# DorothiController.net
KiCad netlist of a schematic drawn in EAGLE
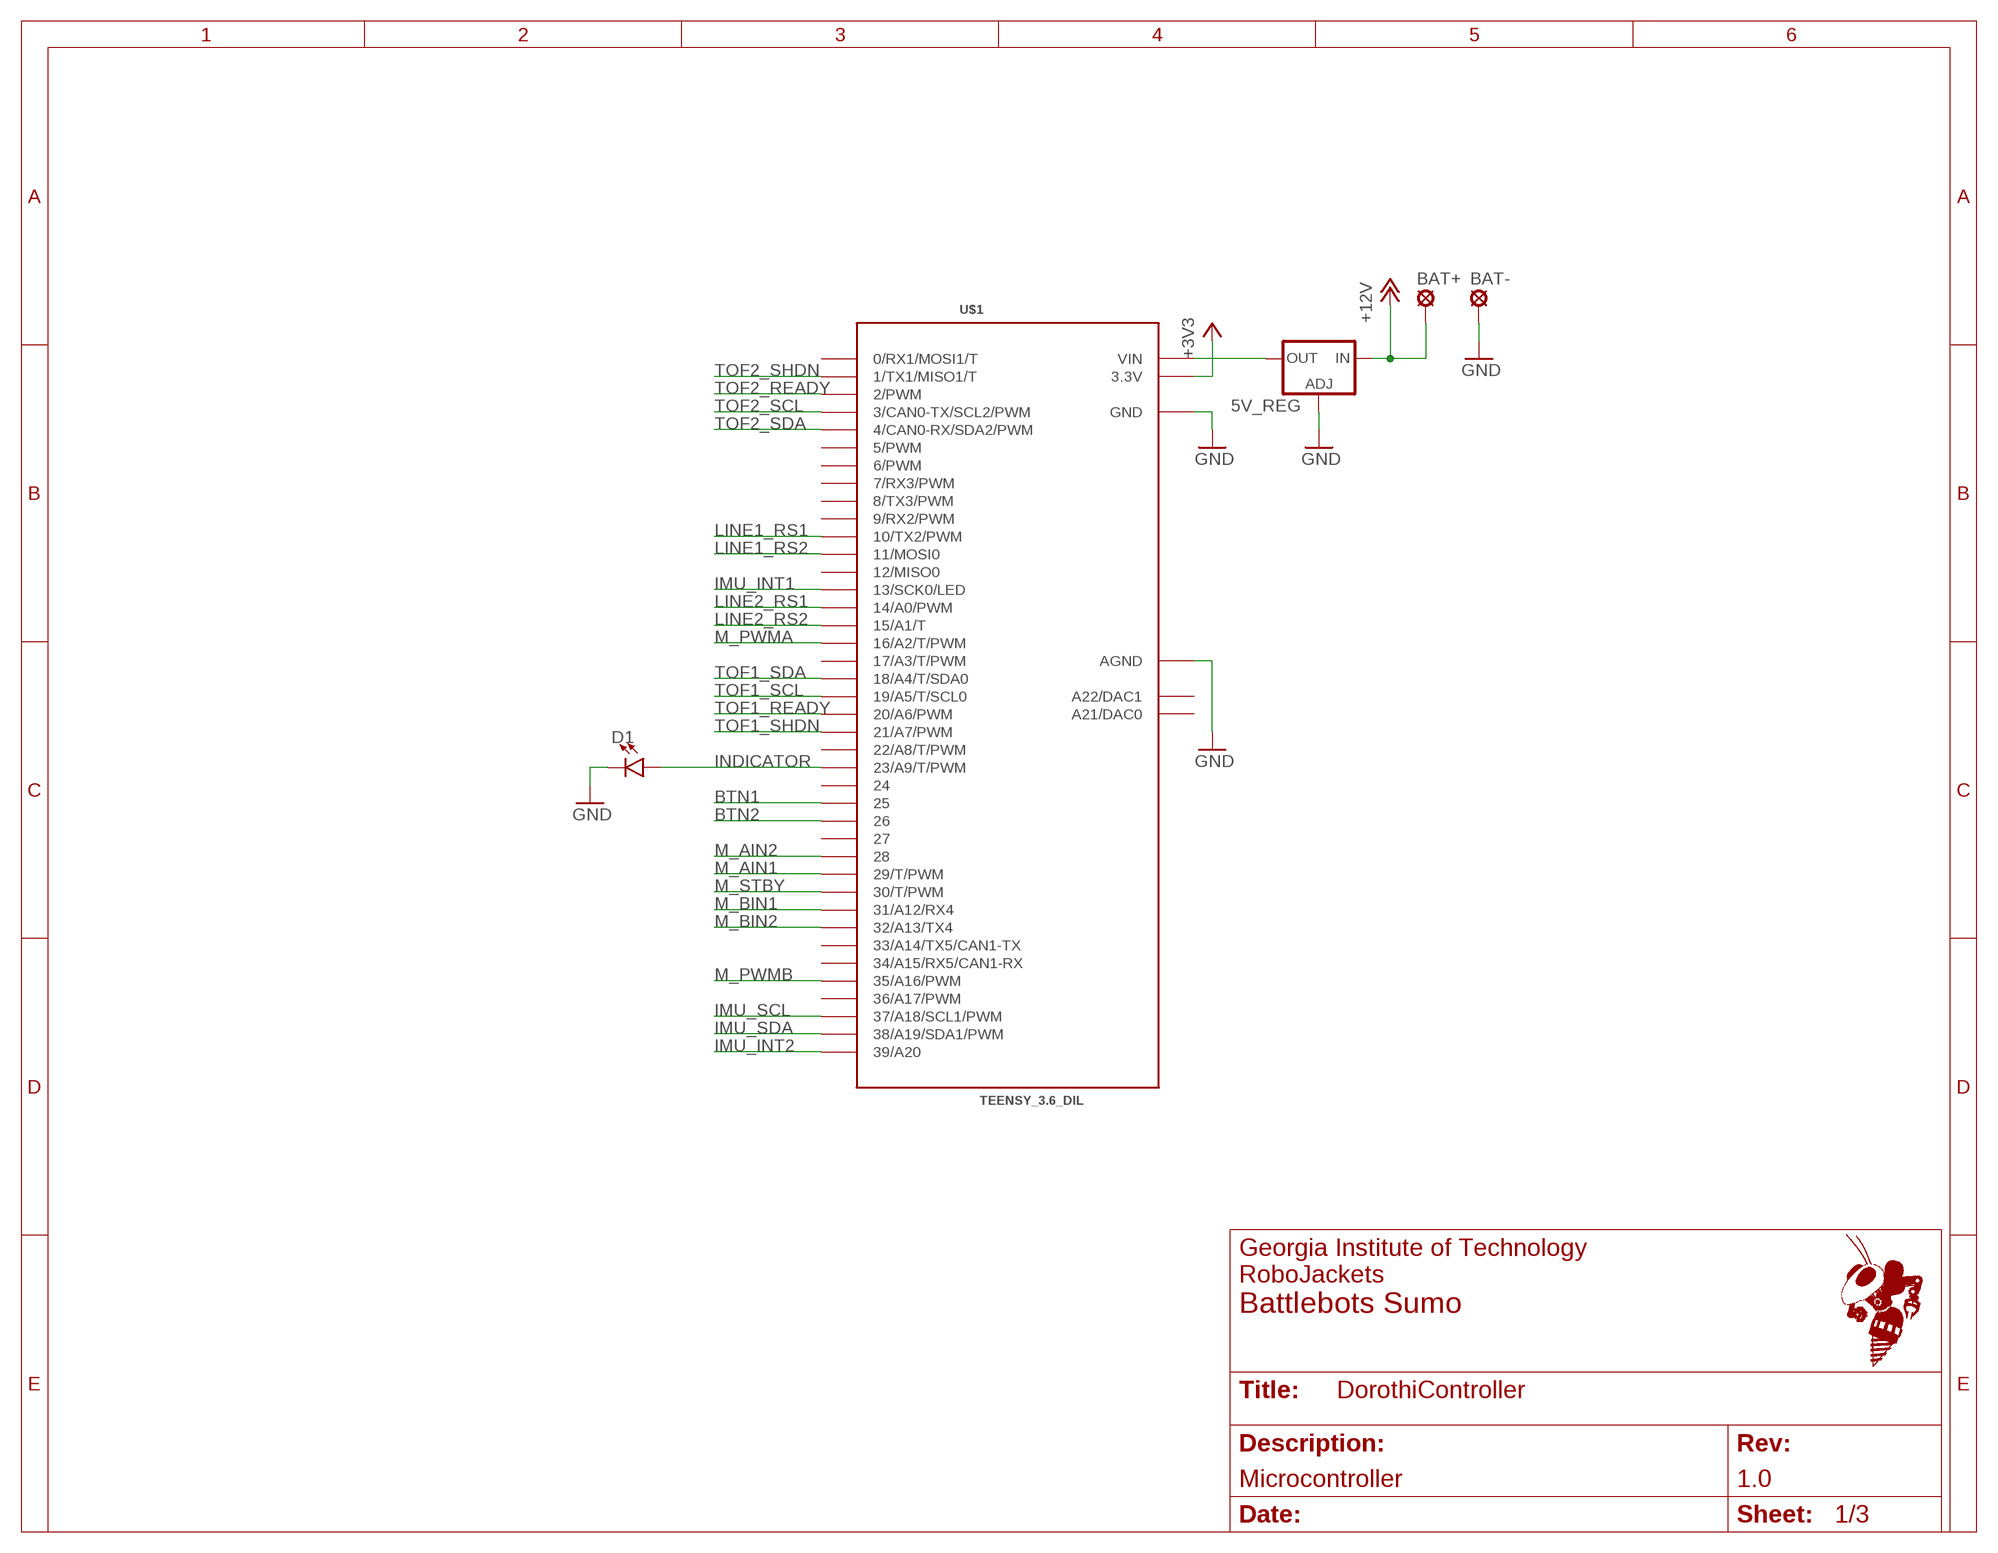
[diagram p0: schematic, sheet 1]
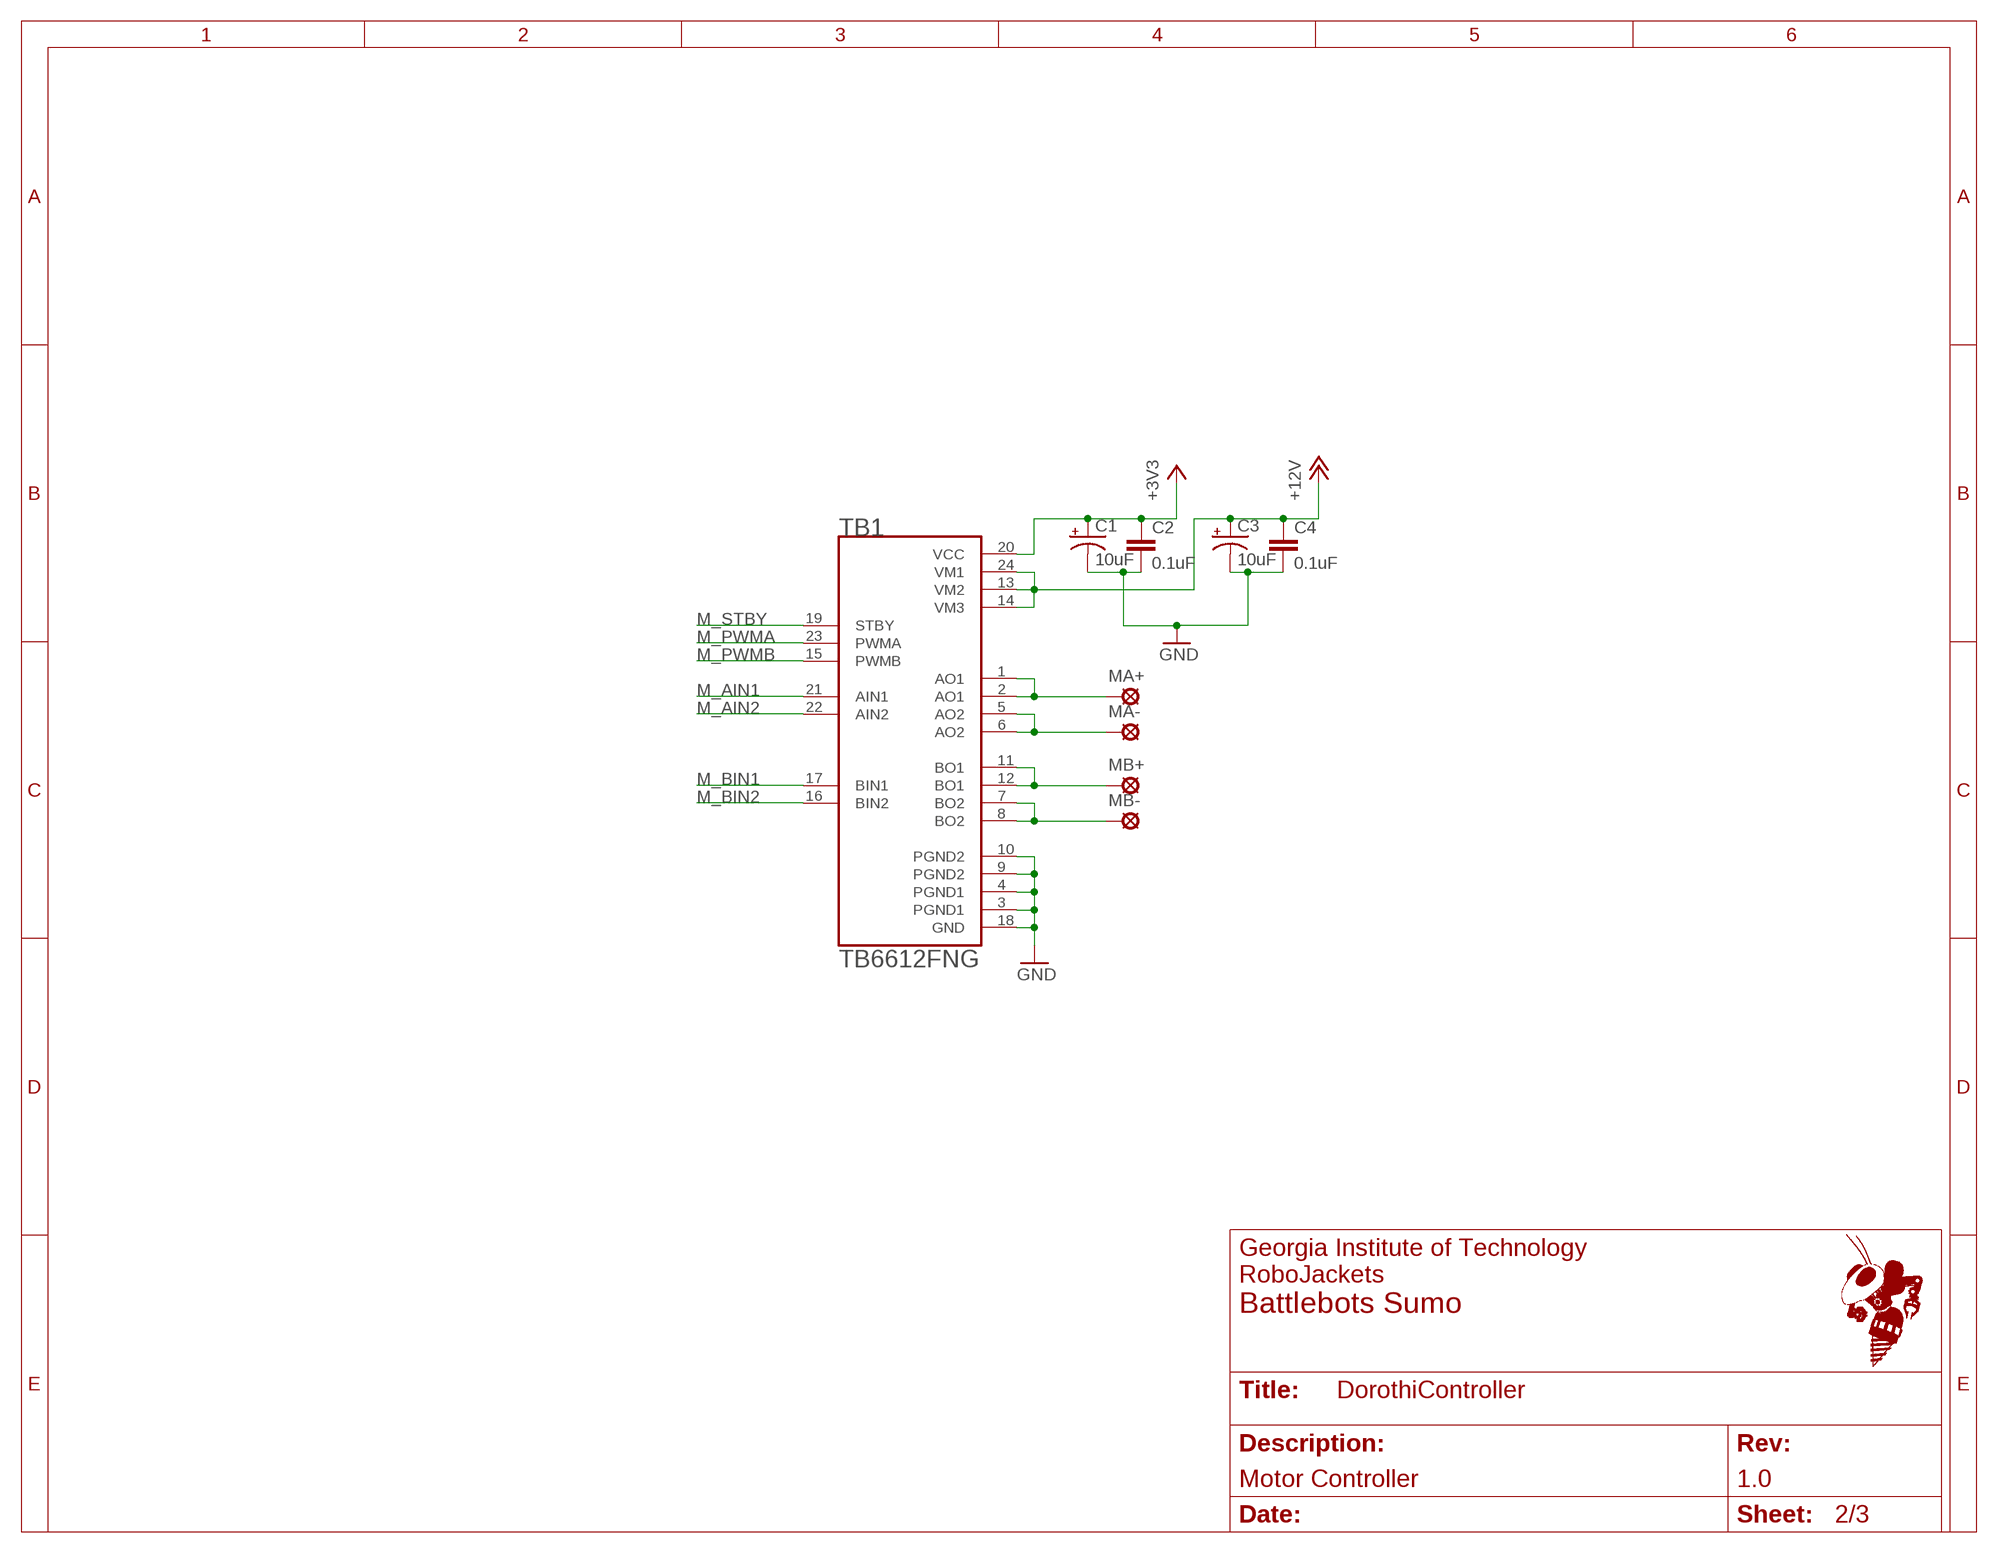
[diagram p1: schematic, sheet 2]
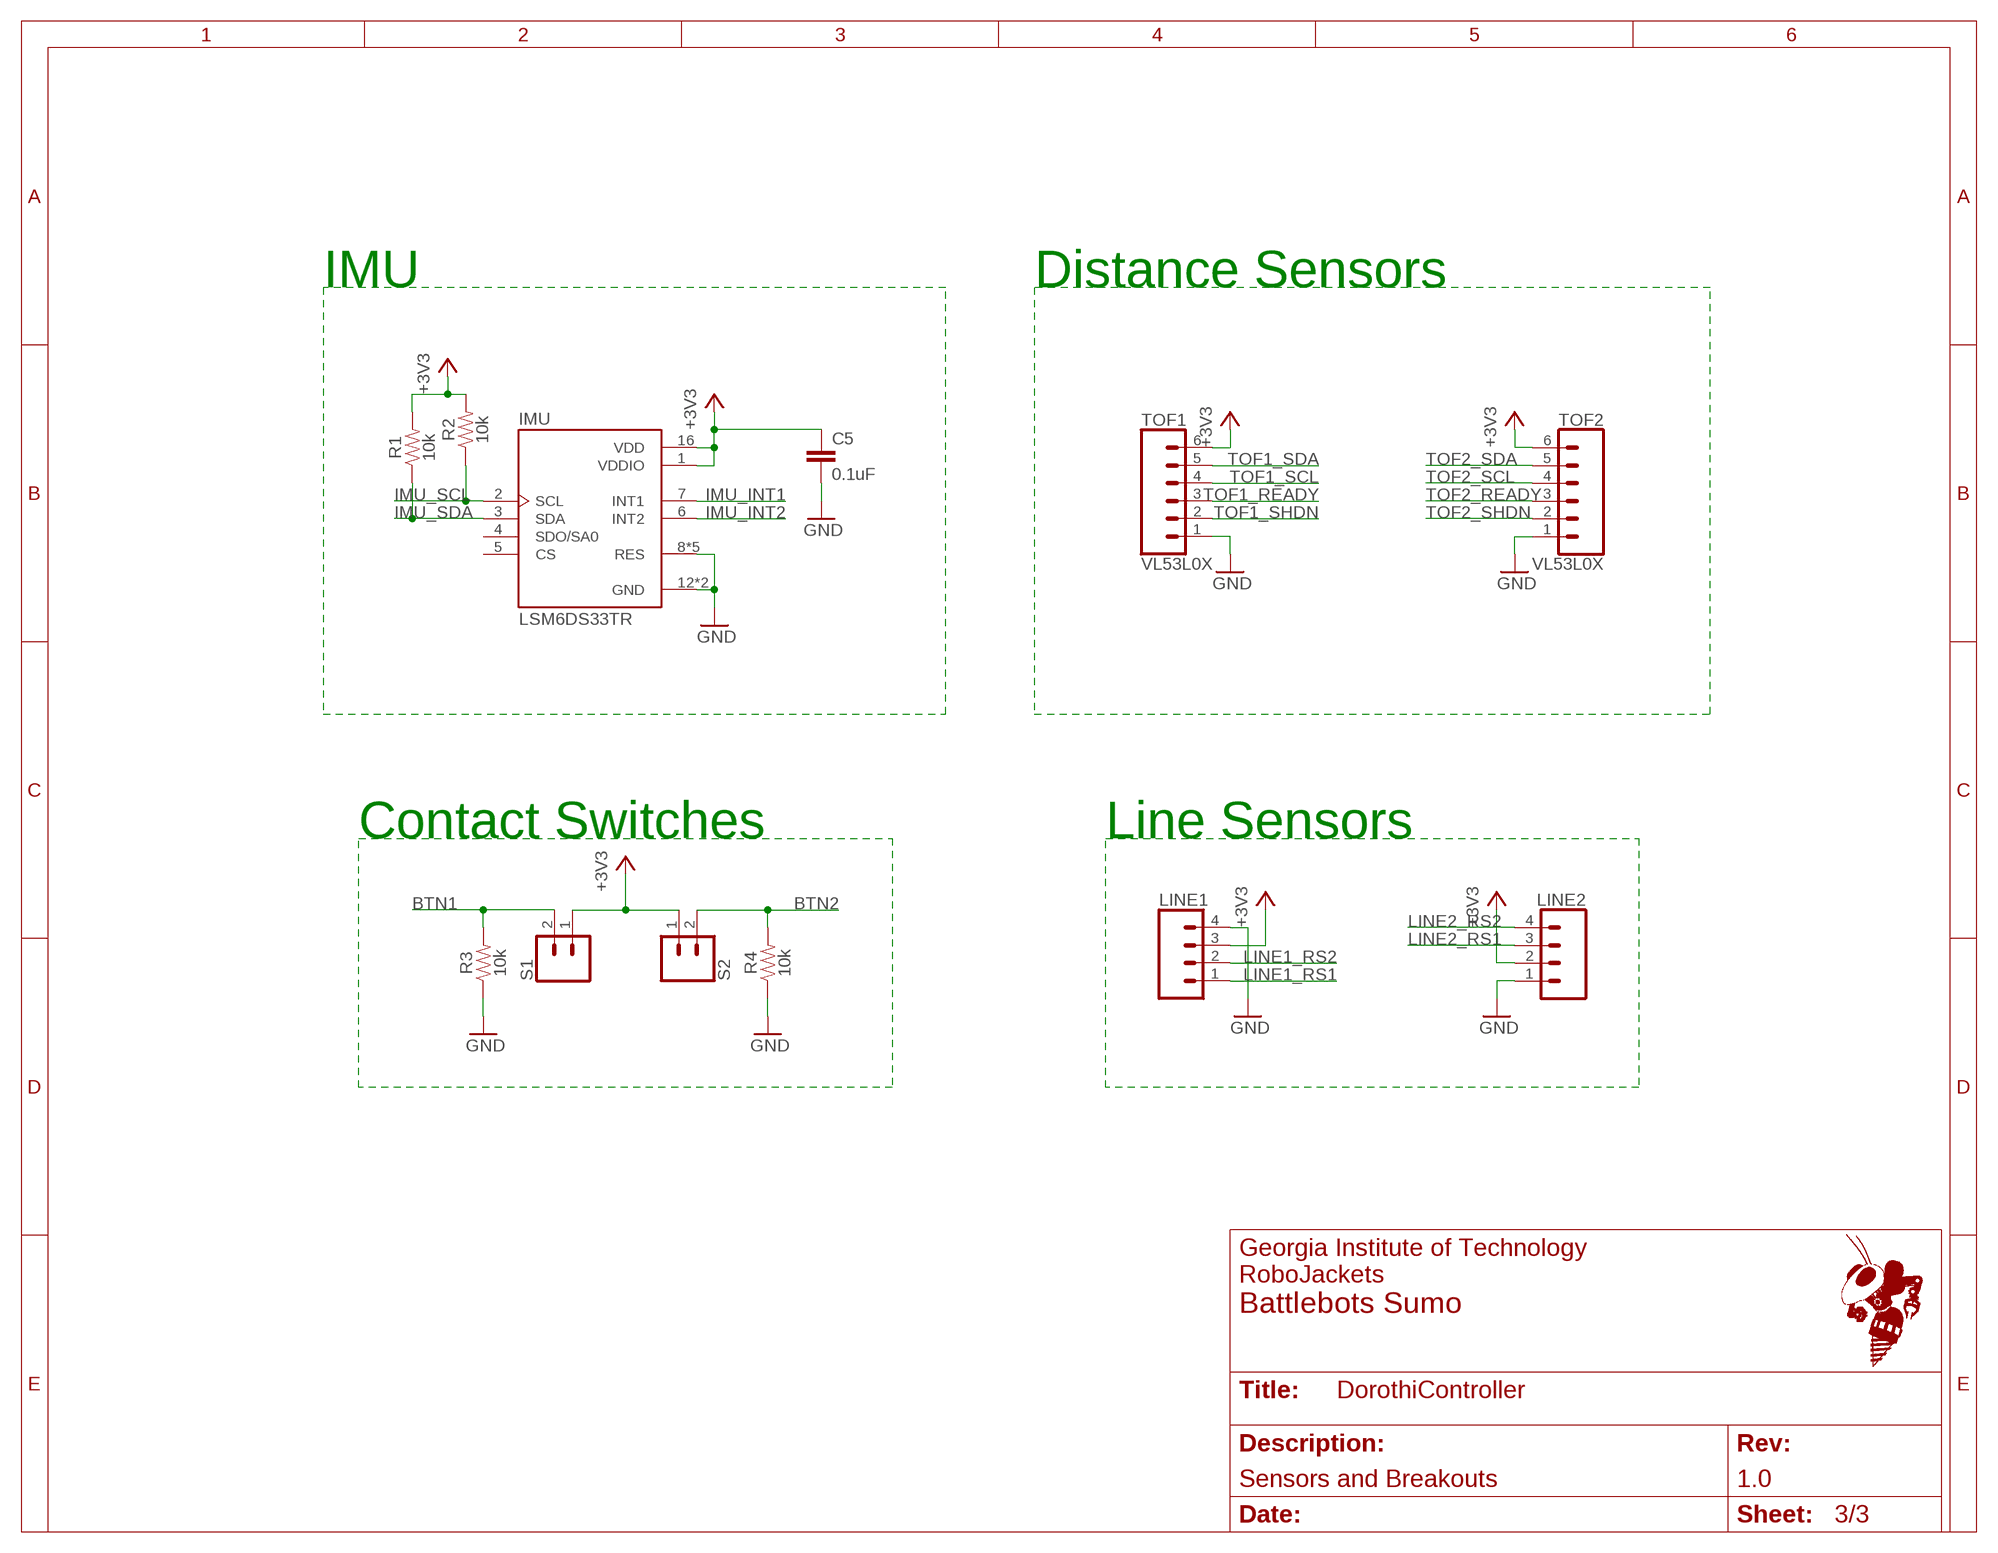
[diagram p2: schematic, sheet 3]

(export (version "E")
  (design (tool "Eeschema 10.0.6"))
  (components
    (comp (ref "5V_REG")
      (value "LM138-TL")
      (footprint "eagle-import:TO220L1")
      (libsource (lib "eagle-import") (part "LM138-TL"))
    )
    (comp (ref "BAT+")
      (value "24_SOLPAD")
      (footprint "eagle-import:WIRE_SOLPAD")
      (libsource (lib "eagle-import") (part "24_SOLPAD"))
    )
    (comp (ref "BAT-")
      (value "24_SOLPAD")
      (footprint "eagle-import:WIRE_SOLPAD")
      (libsource (lib "eagle-import") (part "24_SOLPAD"))
    )
    (comp (ref "D1")
      (value "LED0603")
      (footprint "eagle-import:LED-0603")
      (libsource (lib "eagle-import") (part "LED0603"))
    )
    (comp (ref "U$1")
      (value "TEENSY_3.6_DIL")
      (footprint "eagle-import:TEENSY_3.6_DIL")
      (libsource (lib "eagle-import") (part "TEENSY_3.6_DIL"))
    )
    (comp (ref "C5")
      (value "0.1uF")
      (footprint "eagle-import:0603")
      (libsource (lib "eagle-import") (part "0.1UF-0603-25V-5%"))
    )
    (comp (ref "IMU")
      (value "LSM6DS33TR")
      (footprint "eagle-import:PQFN50P300X300X86-16N")
      (fields (field (name "MF") "STMicroelectronics"))
      (libsource (lib "eagle-import") (part "LSM6DS33TR"))
    )
    (comp (ref "LINE1")
      (value "CONN_04")
      (footprint "eagle-import:1X04")
      (libsource (lib "eagle-import") (part "CONN_04"))
    )
    (comp (ref "LINE2")
      (value "CONN_04")
      (footprint "eagle-import:1X04")
      (libsource (lib "eagle-import") (part "CONN_04"))
    )
    (comp (ref "R1")
      (value "10k")
      (footprint "eagle-import:0603")
      (libsource (lib "eagle-import") (part "10KOHM-0603-1/10W-1%"))
    )
    (comp (ref "R2")
      (value "10k")
      (footprint "eagle-import:0603")
      (libsource (lib "eagle-import") (part "10KOHM-0603-1/10W-1%"))
    )
    (comp (ref "R3")
      (value "10k")
      (footprint "eagle-import:0603")
      (libsource (lib "eagle-import") (part "10KOHM-0603-1/10W-1%"))
    )
    (comp (ref "R4")
      (value "10k")
      (footprint "eagle-import:0603")
      (libsource (lib "eagle-import") (part "10KOHM-0603-1/10W-1%"))
    )
    (comp (ref "S1")
      (value "CONN_02")
      (footprint "eagle-import:1X02")
      (libsource (lib "eagle-import") (part "CONN_02"))
    )
    (comp (ref "S2")
      (value "CONN_02")
      (footprint "eagle-import:1X02")
      (libsource (lib "eagle-import") (part "CONN_02"))
    )
    (comp (ref "TOF1")
      (value "VL53L0X")
      (footprint "eagle-import:1X06")
      (libsource (lib "eagle-import") (part "CONN_06SILK_FEMALE_PTH"))
    )
    (comp (ref "TOF2")
      (value "VL53L0X")
      (footprint "eagle-import:1X06")
      (libsource (lib "eagle-import") (part "CONN_06SILK_FEMALE_PTH"))
    )
    (comp (ref "C1")
      (value "10uF")
      (footprint "eagle-import:EIA3528")
      (libsource (lib "eagle-import") (part "10UF-POLAR-EIA3528-20V-10%(TANT)"))
    )
    (comp (ref "C2")
      (value "0.1uF")
      (footprint "eagle-import:0603")
      (libsource (lib "eagle-import") (part "0.1UF-0603-25V-5%"))
    )
    (comp (ref "C3")
      (value "10uF")
      (footprint "eagle-import:EIA3528")
      (libsource (lib "eagle-import") (part "10UF-POLAR-EIA3528-20V-10%(TANT)"))
    )
    (comp (ref "C4")
      (value "0.1uF")
      (footprint "eagle-import:0603")
      (libsource (lib "eagle-import") (part "0.1UF-0603-25V-5%"))
    )
    (comp (ref "MA+")
      (value "24_SOLPAD")
      (footprint "eagle-import:WIRE_SOLPAD")
      (libsource (lib "eagle-import") (part "24_SOLPAD"))
    )
    (comp (ref "MA-")
      (value "24_SOLPAD")
      (footprint "eagle-import:WIRE_SOLPAD")
      (libsource (lib "eagle-import") (part "24_SOLPAD"))
    )
    (comp (ref "MB+")
      (value "24_SOLPAD")
      (footprint "eagle-import:WIRE_SOLPAD")
      (libsource (lib "eagle-import") (part "24_SOLPAD"))
    )
    (comp (ref "MB-")
      (value "24_SOLPAD")
      (footprint "eagle-import:WIRE_SOLPAD")
      (libsource (lib "eagle-import") (part "24_SOLPAD"))
    )
    (comp (ref "TB1")
      (value "TB6612FNG")
      (footprint "eagle-import:SOP65P760X160-24N")
      (fields (field (name "MF") "Toshiba") (field (name "MP") "TB6612FNG_O,C,8,EL"))
      (libsource (lib "eagle-import") (part "TB6612FNG(O,C,8,EL"))
    )
  )
  (nets
    (net (code "1") (name "+3V3") (class "Default")
      (node (ref "C1") (pin "A") (pinfunction "+_A") (pintype "passive"))
      (node (ref "C2") (pin "1") (pinfunction "1_1") (pintype "passive"))
      (node (ref "C5") (pin "1") (pinfunction "1_1") (pintype "passive"))
      (node (ref "IMU") (pin "1") (pinfunction "VDDIO_1") (pintype "power_in"))
      (node (ref "IMU") (pin "16") (pinfunction "VDD_16") (pintype "power_in"))
      (node (ref "LINE1") (pin "3") (pinfunction "3_3") (pintype "passive"))
      (node (ref "LINE2") (pin "2") (pinfunction "2_2") (pintype "passive"))
      (node (ref "R1") (pin "2") (pinfunction "2_2") (pintype "passive"))
      (node (ref "R2") (pin "2") (pinfunction "2_2") (pintype "passive"))
      (node (ref "S1") (pin "1") (pinfunction "1_1") (pintype "passive"))
      (node (ref "S2") (pin "1") (pinfunction "1_1") (pintype "passive"))
      (node (ref "TB1") (pin "20") (pinfunction "VCC_20") (pintype "power_in"))
      (node (ref "TOF1") (pin "6") (pinfunction "6_6") (pintype "passive"))
      (node (ref "TOF2") (pin "6") (pinfunction "6_6") (pintype "passive"))
      (node (ref "U$1") (pin "3.3V") (pinfunction "3.3V_3.3V") (pintype "power_in"))
      (node (ref "U$1") (pin "3.3V3") (pinfunction "3.3V_3.3V3") (pintype "power_in"))
    )
    (net (code "2") (name "+12V") (class "Default")
      (node (ref "5V_REG") (pin "3") (pinfunction "IN_3") (pintype "input"))
      (node (ref "BAT+") (pin "P$1") (pinfunction "MP_P$1") (pintype "passive"))
      (node (ref "C3") (pin "A") (pinfunction "+_A") (pintype "passive"))
      (node (ref "C4") (pin "1") (pinfunction "1_1") (pintype "passive"))
      (node (ref "TB1") (pin "13") (pinfunction "VM2_13") (pintype "power_in"))
      (node (ref "TB1") (pin "14") (pinfunction "VM3_14") (pintype "power_in"))
      (node (ref "TB1") (pin "24") (pinfunction "VM1_24") (pintype "power_in"))
    )
    (net (code "3") (name "BTN1") (class "Default")
      (node (ref "R3") (pin "2") (pinfunction "2_2") (pintype "passive"))
      (node (ref "S1") (pin "2") (pinfunction "2_2") (pintype "passive"))
      (node (ref "U$1") (pin "25") (pinfunction "25_25") (pintype "bidirectional"))
    )
    (net (code "4") (name "BTN2") (class "Default")
      (node (ref "R4") (pin "2") (pinfunction "2_2") (pintype "passive"))
      (node (ref "S2") (pin "2") (pinfunction "2_2") (pintype "passive"))
      (node (ref "U$1") (pin "26") (pinfunction "26_26") (pintype "bidirectional"))
    )
    (net (code "5") (name "GND") (class "Default")
      (node (ref "5V_REG") (pin "1") (pinfunction "ADJ_1") (pintype "input"))
      (node (ref "BAT-") (pin "P$1") (pinfunction "MP_P$1") (pintype "passive"))
      (node (ref "C1") (pin "C") (pinfunction "-_C") (pintype "passive"))
      (node (ref "C2") (pin "2") (pinfunction "2_2") (pintype "passive"))
      (node (ref "C3") (pin "C") (pinfunction "-_C") (pintype "passive"))
      (node (ref "C4") (pin "2") (pinfunction "2_2") (pintype "passive"))
      (node (ref "C5") (pin "2") (pinfunction "2_2") (pintype "passive"))
      (node (ref "D1") (pin "C") (pinfunction "C_C") (pintype "passive"))
      (node (ref "IMU") (pin "10") (pinfunction "RES_10") (pintype "passive"))
      (node (ref "IMU") (pin "11") (pinfunction "RES_11") (pintype "passive"))
      (node (ref "IMU") (pin "12") (pinfunction "GND_12") (pintype "power_in"))
      (node (ref "IMU") (pin "13") (pinfunction "GND_13") (pintype "power_in"))
      (node (ref "IMU") (pin "15") (pinfunction "RES_15") (pintype "passive"))
      (node (ref "IMU") (pin "8") (pinfunction "RES_8") (pintype "passive"))
      (node (ref "IMU") (pin "9") (pinfunction "RES_9") (pintype "passive"))
      (node (ref "LINE1") (pin "4") (pinfunction "4_4") (pintype "passive"))
      (node (ref "LINE2") (pin "1") (pinfunction "1_1") (pintype "passive"))
      (node (ref "R3") (pin "1") (pinfunction "1_1") (pintype "passive"))
      (node (ref "R4") (pin "1") (pinfunction "1_1") (pintype "passive"))
      (node (ref "TB1") (pin "10") (pinfunction "PGND2_10") (pintype "passive"))
      (node (ref "TB1") (pin "18") (pinfunction "GND_18") (pintype "passive"))
      (node (ref "TB1") (pin "3") (pinfunction "PGND1_3") (pintype "passive"))
      (node (ref "TB1") (pin "4") (pinfunction "PGND1_4") (pintype "passive"))
      (node (ref "TB1") (pin "9") (pinfunction "PGND2_9") (pintype "passive"))
      (node (ref "TOF1") (pin "1") (pinfunction "1_1") (pintype "passive"))
      (node (ref "TOF2") (pin "1") (pinfunction "1_1") (pintype "passive"))
      (node (ref "U$1") (pin "AGND") (pinfunction "AGND_AGND") (pintype "power_in"))
      (node (ref "U$1") (pin "GND") (pinfunction "GND_GND") (pintype "power_in"))
      (node (ref "U$1") (pin "GND1") (pinfunction "GND_GND1") (pintype "power_in"))
    )
    (net (code "6") (name "IMU_INT1") (class "Default")
      (node (ref "IMU") (pin "7") (pinfunction "INT1_7") (pintype "output"))
      (node (ref "U$1") (pin "13") (pinfunction "13/SCK0/LED_13") (pintype "bidirectional"))
    )
    (net (code "7") (name "IMU_INT2") (class "Default")
      (node (ref "IMU") (pin "6") (pinfunction "INT2_6") (pintype "output"))
      (node (ref "U$1") (pin "39/A20") (pinfunction "39/A20_39/A20") (pintype "bidirectional"))
    )
    (net (code "8") (name "IMU_SCL") (class "Default")
      (node (ref "IMU") (pin "2") (pinfunction "SCL_2") (pintype "bidirectional"))
      (node (ref "R2") (pin "1") (pinfunction "1_1") (pintype "passive"))
      (node (ref "U$1") (pin "37/A18") (pinfunction "37/A18/SCL1/PWM_37/A18") (pintype "bidirectional"))
    )
    (net (code "9") (name "IMU_SDA") (class "Default")
      (node (ref "IMU") (pin "3") (pinfunction "SDA_3") (pintype "bidirectional"))
      (node (ref "R1") (pin "1") (pinfunction "1_1") (pintype "passive"))
      (node (ref "U$1") (pin "38/A19") (pinfunction "38/A19/SDA1/PWM_38/A19") (pintype "bidirectional"))
    )
    (net (code "10") (name "INDICATOR") (class "Default")
      (node (ref "D1") (pin "A") (pinfunction "A_A") (pintype "passive"))
      (node (ref "U$1") (pin "23/A9") (pinfunction "23/A9/T/PWM_23/A9") (pintype "bidirectional"))
    )
    (net (code "11") (name "LINE1_RS1") (class "Default")
      (node (ref "LINE1") (pin "1") (pinfunction "1_1") (pintype "passive"))
      (node (ref "U$1") (pin "10") (pinfunction "10/TX2/PWM_10") (pintype "bidirectional"))
    )
    (net (code "12") (name "LINE1_RS2") (class "Default")
      (node (ref "LINE1") (pin "2") (pinfunction "2_2") (pintype "passive"))
      (node (ref "U$1") (pin "11") (pinfunction "11/MOSI0_11") (pintype "bidirectional"))
    )
    (net (code "13") (name "LINE2_RS1") (class "Default")
      (node (ref "LINE2") (pin "3") (pinfunction "3_3") (pintype "passive"))
      (node (ref "U$1") (pin "14/A0") (pinfunction "14/A0/PWM_14/A0") (pintype "bidirectional"))
    )
    (net (code "14") (name "LINE2_RS2") (class "Default")
      (node (ref "LINE2") (pin "4") (pinfunction "4_4") (pintype "passive"))
      (node (ref "U$1") (pin "15/A1") (pinfunction "15/A1/T_15/A1") (pintype "bidirectional"))
    )
    (net (code "15") (name "M_AIN1") (class "Default")
      (node (ref "TB1") (pin "21") (pinfunction "AIN1_21") (pintype "input"))
      (node (ref "U$1") (pin "29") (pinfunction "29/T/PWM_29") (pintype "bidirectional"))
    )
    (net (code "16") (name "M_AIN2") (class "Default")
      (node (ref "TB1") (pin "22") (pinfunction "AIN2_22") (pintype "input"))
      (node (ref "U$1") (pin "28") (pinfunction "28_28") (pintype "bidirectional"))
    )
    (net (code "17") (name "M_BIN1") (class "Default")
      (node (ref "TB1") (pin "17") (pinfunction "BIN1_17") (pintype "input"))
      (node (ref "U$1") (pin "31/A12") (pinfunction "31/A12/RX4_31/A12") (pintype "bidirectional"))
    )
    (net (code "18") (name "M_BIN2") (class "Default")
      (node (ref "TB1") (pin "16") (pinfunction "BIN2_16") (pintype "input"))
      (node (ref "U$1") (pin "32/A13") (pinfunction "32/A13/TX4_32/A13") (pintype "bidirectional"))
    )
    (net (code "19") (name "M_PWMA") (class "Default")
      (node (ref "TB1") (pin "23") (pinfunction "PWMA_23") (pintype "input"))
      (node (ref "U$1") (pin "16/A2") (pinfunction "16/A2/T/PWM_16/A2") (pintype "bidirectional"))
    )
    (net (code "20") (name "M_PWMB") (class "Default")
      (node (ref "TB1") (pin "15") (pinfunction "PWMB_15") (pintype "input"))
      (node (ref "U$1") (pin "35/A16") (pinfunction "35/A16/PWM_35/A16") (pintype "bidirectional"))
    )
    (net (code "21") (name "M_STBY") (class "Default")
      (node (ref "TB1") (pin "19") (pinfunction "STBY_19") (pintype "input"))
      (node (ref "U$1") (pin "30") (pinfunction "30/T/PWM_30") (pintype "bidirectional"))
    )
    (net (code "22") (name "Net-(5V_REG-OUT)") (class "Default")
      (node (ref "5V_REG") (pin "2") (pinfunction "OUT_2") (pintype "passive"))
      (node (ref "U$1") (pin "VIN") (pinfunction "VIN_VIN") (pintype "power_in"))
    )
    (net (code "23") (name "Net-(MA+-MP)") (class "Default")
      (node (ref "MA+") (pin "P$1") (pinfunction "MP_P$1") (pintype "passive"))
      (node (ref "TB1") (pin "1") (pinfunction "AO1_1") (pintype "bidirectional"))
      (node (ref "TB1") (pin "2") (pinfunction "AO1_2") (pintype "bidirectional"))
    )
    (net (code "24") (name "Net-(MA--MP)") (class "Default")
      (node (ref "MA-") (pin "P$1") (pinfunction "MP_P$1") (pintype "passive"))
      (node (ref "TB1") (pin "5") (pinfunction "AO2_5") (pintype "bidirectional"))
      (node (ref "TB1") (pin "6") (pinfunction "AO2_6") (pintype "bidirectional"))
    )
    (net (code "25") (name "Net-(MB+-MP)") (class "Default")
      (node (ref "MB+") (pin "P$1") (pinfunction "MP_P$1") (pintype "passive"))
      (node (ref "TB1") (pin "11") (pinfunction "BO1_11") (pintype "bidirectional"))
      (node (ref "TB1") (pin "12") (pinfunction "BO1_12") (pintype "bidirectional"))
    )
    (net (code "26") (name "Net-(MB--MP)") (class "Default")
      (node (ref "MB-") (pin "P$1") (pinfunction "MP_P$1") (pintype "passive"))
      (node (ref "TB1") (pin "7") (pinfunction "BO2_7") (pintype "bidirectional"))
      (node (ref "TB1") (pin "8") (pinfunction "BO2_8") (pintype "bidirectional"))
    )
    (net (code "27") (name "TOF1_READY") (class "Default")
      (node (ref "TOF1") (pin "3") (pinfunction "3_3") (pintype "passive"))
      (node (ref "U$1") (pin "20/A6") (pinfunction "20/A6/PWM_20/A6") (pintype "bidirectional"))
    )
    (net (code "28") (name "TOF1_SCL") (class "Default")
      (node (ref "TOF1") (pin "4") (pinfunction "4_4") (pintype "passive"))
      (node (ref "U$1") (pin "19/A5") (pinfunction "19/A5/T/SCL0_19/A5") (pintype "bidirectional"))
    )
    (net (code "29") (name "TOF1_SDA") (class "Default")
      (node (ref "TOF1") (pin "5") (pinfunction "5_5") (pintype "passive"))
      (node (ref "U$1") (pin "18/A4") (pinfunction "18/A4/T/SDA0_18/A4") (pintype "bidirectional"))
    )
    (net (code "30") (name "TOF1_SHDN") (class "Default")
      (node (ref "TOF1") (pin "2") (pinfunction "2_2") (pintype "passive"))
      (node (ref "U$1") (pin "21/A7") (pinfunction "21/A7/PWM_21/A7") (pintype "bidirectional"))
    )
    (net (code "31") (name "TOF2_READY") (class "Default")
      (node (ref "TOF2") (pin "3") (pinfunction "3_3") (pintype "passive"))
      (node (ref "U$1") (pin "2") (pinfunction "2/PWM_2") (pintype "bidirectional"))
    )
    (net (code "32") (name "TOF2_SCL") (class "Default")
      (node (ref "TOF2") (pin "4") (pinfunction "4_4") (pintype "passive"))
      (node (ref "U$1") (pin "3") (pinfunction "3/CAN0-TX/SCL2/PWM_3") (pintype "bidirectional"))
    )
    (net (code "33") (name "TOF2_SDA") (class "Default")
      (node (ref "TOF2") (pin "5") (pinfunction "5_5") (pintype "passive"))
      (node (ref "U$1") (pin "4") (pinfunction "4/CAN0-RX/SDA2/PWM_4") (pintype "bidirectional"))
    )
    (net (code "34") (name "TOF2_SHDN") (class "Default")
      (node (ref "TOF2") (pin "2") (pinfunction "2_2") (pintype "passive"))
      (node (ref "U$1") (pin "1") (pinfunction "1/TX1/MISO1/T_1") (pintype "bidirectional"))
    )
    (net (code "35") (name "unconnected-(IMU-CS-Pad5)") (class "Default")
      (node (ref "IMU") (pin "5") (pinfunction "CS_5") (pintype "bidirectional"))
    )
    (net (code "36") (name "unconnected-(IMU-SDO{slash}SA0-Pad4)") (class "Default")
      (node (ref "IMU") (pin "4") (pinfunction "SDO/SA0_4") (pintype "bidirectional"))
    )
    (net (code "37") (name "unconnected-(U$1-0{slash}RX1{slash}MOSI1{slash}T-Pad0)") (class "Default")
      (node (ref "U$1") (pin "0") (pinfunction "0/RX1/MOSI1/T_0") (pintype "bidirectional"))
    )
    (net (code "38") (name "unconnected-(U$1-5{slash}PWM-Pad5)") (class "Default")
      (node (ref "U$1") (pin "5") (pinfunction "5/PWM_5") (pintype "bidirectional"))
    )
    (net (code "39") (name "unconnected-(U$1-6{slash}PWM-Pad6)") (class "Default")
      (node (ref "U$1") (pin "6") (pinfunction "6/PWM_6") (pintype "bidirectional"))
    )
    (net (code "40") (name "unconnected-(U$1-7{slash}RX3{slash}PWM-Pad7)") (class "Default")
      (node (ref "U$1") (pin "7") (pinfunction "7/RX3/PWM_7") (pintype "bidirectional"))
    )
    (net (code "41") (name "unconnected-(U$1-8{slash}TX3{slash}PWM-Pad8)") (class "Default")
      (node (ref "U$1") (pin "8") (pinfunction "8/TX3/PWM_8") (pintype "bidirectional"))
    )
    (net (code "42") (name "unconnected-(U$1-9{slash}RX2{slash}PWM-Pad9)") (class "Default")
      (node (ref "U$1") (pin "9") (pinfunction "9/RX2/PWM_9") (pintype "bidirectional"))
    )
    (net (code "43") (name "unconnected-(U$1-12{slash}MISO0-Pad12)") (class "Default")
      (node (ref "U$1") (pin "12") (pinfunction "12/MISO0_12") (pintype "bidirectional"))
    )
    (net (code "44") (name "unconnected-(U$1-17{slash}A3{slash}T{slash}PWM-Pad17{slash}A3)") (class "Default")
      (node (ref "U$1") (pin "17/A3") (pinfunction "17/A3/T/PWM_17/A3") (pintype "bidirectional"))
    )
    (net (code "45") (name "unconnected-(U$1-22{slash}A8{slash}T{slash}PWM-Pad22{slash}A8)") (class "Default")
      (node (ref "U$1") (pin "22/A8") (pinfunction "22/A8/T/PWM_22/A8") (pintype "bidirectional"))
    )
    (net (code "46") (name "unconnected-(U$1-33{slash}A14{slash}TX5{slash}CAN1-TX-Pad33{slash}A14)") (class "Default")
      (node (ref "U$1") (pin "33/A14") (pinfunction "33/A14/TX5/CAN1-TX_33/A14") (pintype "bidirectional"))
    )
    (net (code "47") (name "unconnected-(U$1-34{slash}A15{slash}RX5{slash}CAN1-RX-Pad34{slash}A15)") (class "Default")
      (node (ref "U$1") (pin "34/A15") (pinfunction "34/A15/RX5/CAN1-RX_34/A15") (pintype "bidirectional"))
    )
    (net (code "48") (name "unconnected-(U$1-36{slash}A17{slash}PWM-Pad36{slash}A17)") (class "Default")
      (node (ref "U$1") (pin "36/A17") (pinfunction "36/A17/PWM_36/A17") (pintype "bidirectional"))
    )
    (net (code "49") (name "unconnected-(U$1-A21{slash}DAC0-PadA21)") (class "Default")
      (node (ref "U$1") (pin "A21") (pinfunction "A21/DAC0_A21") (pintype "bidirectional"))
    )
    (net (code "50") (name "unconnected-(U$1-A22{slash}DAC1-PadA22)") (class "Default")
      (node (ref "U$1") (pin "A22") (pinfunction "A22/DAC1_A22") (pintype "bidirectional"))
    )
    (net (code "51") (name "unconnected-(U$1-Pad24)") (class "Default")
      (node (ref "U$1") (pin "24") (pinfunction "24_24") (pintype "bidirectional"))
    )
    (net (code "52") (name "unconnected-(U$1-Pad27)") (class "Default")
      (node (ref "U$1") (pin "27") (pinfunction "27_27") (pintype "bidirectional"))
    )
  )
)
